# P_13_BOOT_CFG.net
KiCad netlist of a schematic drawn in Altium Designer
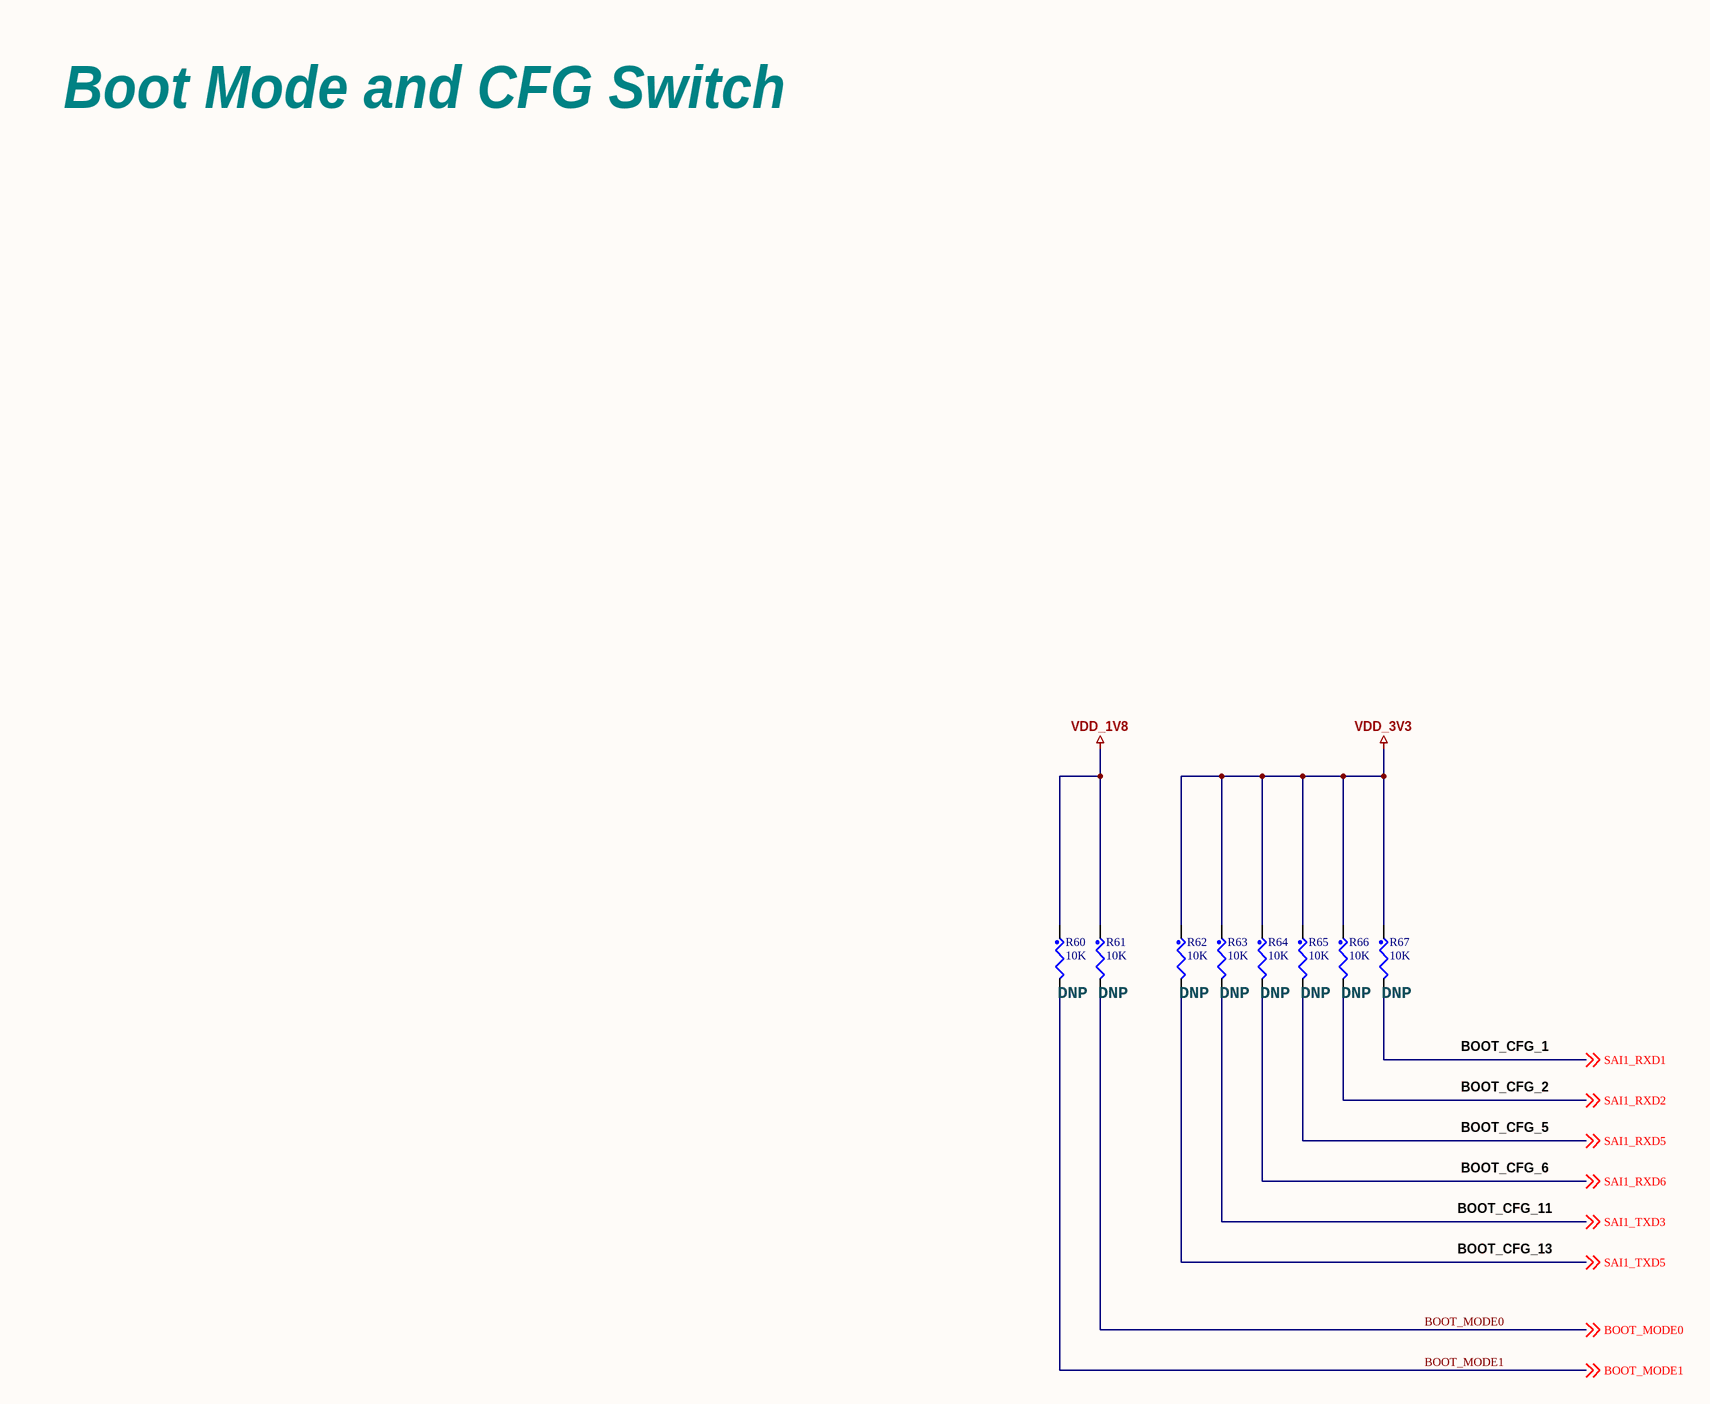
[diagram p0: P[13]BOOT_CFG.SchDoc]

(export (version "E")
  (design (tool "Eeschema 10.0.6"))
  (components
    (comp (ref "R60") (value "10K") (footprint "0402_CC") (libsource (lib "AA_iMX8_M_") (part "RES")))
    (comp (ref "R61") (value "10K") (footprint "0402_CC") (libsource (lib "AA_iMX8_M_") (part "RES")))
    (comp (ref "R62") (value "10K") (footprint "0402_CC") (libsource (lib "AA_iMX8_M_") (part "RES")))
    (comp (ref "R63") (value "10K") (footprint "0402_CC") (libsource (lib "AA_iMX8_M_") (part "RES")))
    (comp (ref "R64") (value "10K") (footprint "0402_CC") (libsource (lib "AA_iMX8_M_") (part "RES")))
    (comp (ref "R65") (value "10K") (footprint "0402_CC") (libsource (lib "AA_iMX8_M_") (part "RES")))
    (comp (ref "R66") (value "10K") (footprint "0402_CC") (libsource (lib "AA_iMX8_M_") (part "RES")))
    (comp (ref "R67") (value "10K") (footprint "0402_CC") (libsource (lib "AA_iMX8_M_") (part "RES")))
  )
  (nets
    (net (code "1") (name "BOOT_MODE0") (class "Default")
      (node (ref "R61") (pin "2") (pinfunction "2_2") (pintype "passive"))
    )
    (net (code "2") (name "BOOT_MODE1") (class "Default")
      (node (ref "R60") (pin "2") (pinfunction "2_2") (pintype "passive"))
    )
    (net (code "3") (name "SAI1_RXD1") (class "Default")
      (node (ref "R67") (pin "2") (pinfunction "2_2") (pintype "passive"))
    )
    (net (code "4") (name "SAI1_RXD2") (class "Default")
      (node (ref "R66") (pin "2") (pinfunction "2_2") (pintype "passive"))
    )
    (net (code "5") (name "SAI1_RXD5") (class "Default")
      (node (ref "R65") (pin "2") (pinfunction "2_2") (pintype "passive"))
    )
    (net (code "6") (name "SAI1_RXD6") (class "Default")
      (node (ref "R64") (pin "2") (pinfunction "2_2") (pintype "passive"))
    )
    (net (code "7") (name "SAI1_TXD3") (class "Default")
      (node (ref "R63") (pin "2") (pinfunction "2_2") (pintype "passive"))
    )
    (net (code "8") (name "SAI1_TXD5") (class "Default")
      (node (ref "R62") (pin "2") (pinfunction "2_2") (pintype "passive"))
    )
    (net (code "9") (name "VDD_1V8") (class "Default")
      (node (ref "R60") (pin "1") (pinfunction "1_1") (pintype "passive"))
      (node (ref "R61") (pin "1") (pinfunction "1_1") (pintype "passive"))
    )
    (net (code "10") (name "VDD_3V3") (class "Default")
      (node (ref "R62") (pin "1") (pinfunction "1_1") (pintype "passive"))
      (node (ref "R63") (pin "1") (pinfunction "1_1") (pintype "passive"))
      (node (ref "R64") (pin "1") (pinfunction "1_1") (pintype "passive"))
      (node (ref "R65") (pin "1") (pinfunction "1_1") (pintype "passive"))
      (node (ref "R66") (pin "1") (pinfunction "1_1") (pintype "passive"))
      (node (ref "R67") (pin "1") (pinfunction "1_1") (pintype "passive"))
    )
  )
)
